# Rx_TSOP.net
KiCad netlist of a schematic drawn in Altium Designer
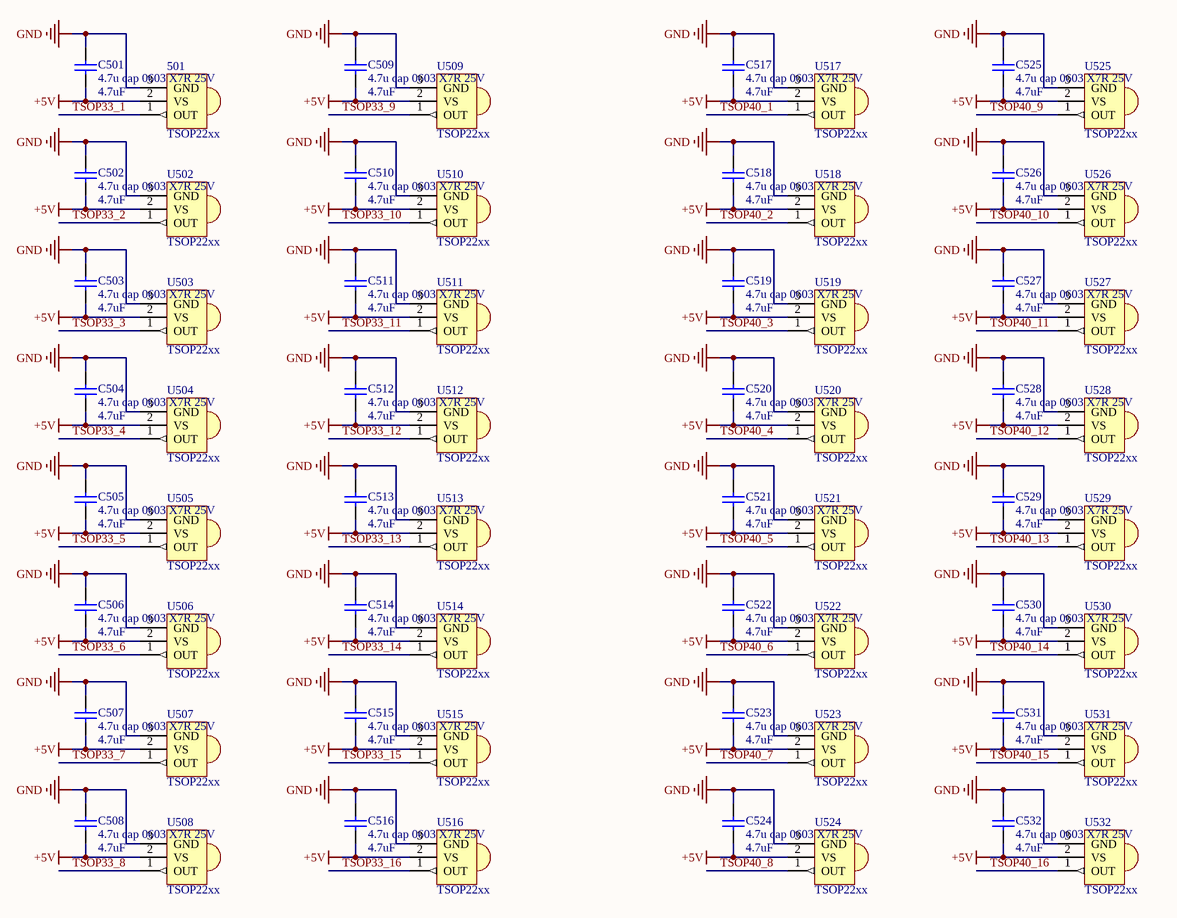
[diagram p0: Rx_TSOP.SchDoc]

(export (version "E")
  (design (tool "Eeschema 10.0.6"))
  (components
    (comp (ref "501")
      (value "TSOP22xx")
      (footprint "TSOP22xx")
      (description "IR Receiver Modules for Remote Control Systems")
      (libsource (lib "Oufff_Lib2") (part "TSOP22xx"))
    )
    (comp (ref "C501")
      (value "4.7u cap 0603 X7R 25V")
      (footprint "0603")
      (description "Capacitor")
      (fields (field (name "ALTIUM_VALUE") "4.7uF") (field (name "PUBLISHER") "Altium Limited"))
      (libsource (lib "Miscellaneous Devices") (part "Cap"))
    )
    (comp (ref "C502")
      (value "4.7u cap 0603 X7R 25V")
      (footprint "0603")
      (description "Capacitor")
      (fields (field (name "ALTIUM_VALUE") "4.7uF") (field (name "PUBLISHER") "Altium Limited"))
      (libsource (lib "Miscellaneous Devices") (part "Cap"))
    )
    (comp (ref "C503")
      (value "4.7u cap 0603 X7R 25V")
      (footprint "0603")
      (description "Capacitor")
      (fields (field (name "ALTIUM_VALUE") "4.7uF") (field (name "PUBLISHER") "Altium Limited"))
      (libsource (lib "Miscellaneous Devices") (part "Cap"))
    )
    (comp (ref "C504")
      (value "4.7u cap 0603 X7R 25V")
      (footprint "0603")
      (description "Capacitor")
      (fields (field (name "ALTIUM_VALUE") "4.7uF") (field (name "PUBLISHER") "Altium Limited"))
      (libsource (lib "Miscellaneous Devices") (part "Cap"))
    )
    (comp (ref "C505")
      (value "4.7u cap 0603 X7R 25V")
      (footprint "0603")
      (description "Capacitor")
      (fields (field (name "ALTIUM_VALUE") "4.7uF") (field (name "PUBLISHER") "Altium Limited"))
      (libsource (lib "Miscellaneous Devices") (part "Cap"))
    )
    (comp (ref "C506")
      (value "4.7u cap 0603 X7R 25V")
      (footprint "0603")
      (description "Capacitor")
      (fields (field (name "ALTIUM_VALUE") "4.7uF") (field (name "PUBLISHER") "Altium Limited"))
      (libsource (lib "Miscellaneous Devices") (part "Cap"))
    )
    (comp (ref "C507")
      (value "4.7u cap 0603 X7R 25V")
      (footprint "0603")
      (description "Capacitor")
      (fields (field (name "ALTIUM_VALUE") "4.7uF") (field (name "PUBLISHER") "Altium Limited"))
      (libsource (lib "Miscellaneous Devices") (part "Cap"))
    )
    (comp (ref "C508")
      (value "4.7u cap 0603 X7R 25V")
      (footprint "0603")
      (description "Capacitor")
      (fields (field (name "ALTIUM_VALUE") "4.7uF") (field (name "PUBLISHER") "Altium Limited"))
      (libsource (lib "Miscellaneous Devices") (part "Cap"))
    )
    (comp (ref "C509")
      (value "4.7u cap 0603 X7R 25V")
      (footprint "0603")
      (description "Capacitor")
      (fields (field (name "ALTIUM_VALUE") "4.7uF") (field (name "PUBLISHER") "Altium Limited"))
      (libsource (lib "Miscellaneous Devices") (part "Cap"))
    )
    (comp (ref "C510")
      (value "4.7u cap 0603 X7R 25V")
      (footprint "0603")
      (description "Capacitor")
      (fields (field (name "ALTIUM_VALUE") "4.7uF") (field (name "PUBLISHER") "Altium Limited"))
      (libsource (lib "Miscellaneous Devices") (part "Cap"))
    )
    (comp (ref "C511")
      (value "4.7u cap 0603 X7R 25V")
      (footprint "0603")
      (description "Capacitor")
      (fields (field (name "ALTIUM_VALUE") "4.7uF") (field (name "PUBLISHER") "Altium Limited"))
      (libsource (lib "Miscellaneous Devices") (part "Cap"))
    )
    (comp (ref "C512")
      (value "4.7u cap 0603 X7R 25V")
      (footprint "0603")
      (description "Capacitor")
      (fields (field (name "ALTIUM_VALUE") "4.7uF") (field (name "PUBLISHER") "Altium Limited"))
      (libsource (lib "Miscellaneous Devices") (part "Cap"))
    )
    (comp (ref "C513")
      (value "4.7u cap 0603 X7R 25V")
      (footprint "0603")
      (description "Capacitor")
      (fields (field (name "ALTIUM_VALUE") "4.7uF") (field (name "PUBLISHER") "Altium Limited"))
      (libsource (lib "Miscellaneous Devices") (part "Cap"))
    )
    (comp (ref "C514")
      (value "4.7u cap 0603 X7R 25V")
      (footprint "0603")
      (description "Capacitor")
      (fields (field (name "ALTIUM_VALUE") "4.7uF") (field (name "PUBLISHER") "Altium Limited"))
      (libsource (lib "Miscellaneous Devices") (part "Cap"))
    )
    (comp (ref "C515")
      (value "4.7u cap 0603 X7R 25V")
      (footprint "0603")
      (description "Capacitor")
      (fields (field (name "ALTIUM_VALUE") "4.7uF") (field (name "PUBLISHER") "Altium Limited"))
      (libsource (lib "Miscellaneous Devices") (part "Cap"))
    )
    (comp (ref "C516")
      (value "4.7u cap 0603 X7R 25V")
      (footprint "0603")
      (description "Capacitor")
      (fields (field (name "ALTIUM_VALUE") "4.7uF") (field (name "PUBLISHER") "Altium Limited"))
      (libsource (lib "Miscellaneous Devices") (part "Cap"))
    )
    (comp (ref "C517")
      (value "4.7u cap 0603 X7R 25V")
      (footprint "0603")
      (description "Capacitor")
      (fields (field (name "ALTIUM_VALUE") "4.7uF") (field (name "PUBLISHER") "Altium Limited"))
      (libsource (lib "Miscellaneous Devices") (part "Cap"))
    )
    (comp (ref "C518")
      (value "4.7u cap 0603 X7R 25V")
      (footprint "0603")
      (description "Capacitor")
      (fields (field (name "ALTIUM_VALUE") "4.7uF") (field (name "PUBLISHER") "Altium Limited"))
      (libsource (lib "Miscellaneous Devices") (part "Cap"))
    )
    (comp (ref "C519")
      (value "4.7u cap 0603 X7R 25V")
      (footprint "0603")
      (description "Capacitor")
      (fields (field (name "ALTIUM_VALUE") "4.7uF") (field (name "PUBLISHER") "Altium Limited"))
      (libsource (lib "Miscellaneous Devices") (part "Cap"))
    )
    (comp (ref "C520")
      (value "4.7u cap 0603 X7R 25V")
      (footprint "0603")
      (description "Capacitor")
      (fields (field (name "ALTIUM_VALUE") "4.7uF") (field (name "PUBLISHER") "Altium Limited"))
      (libsource (lib "Miscellaneous Devices") (part "Cap"))
    )
    (comp (ref "C521")
      (value "4.7u cap 0603 X7R 25V")
      (footprint "0603")
      (description "Capacitor")
      (fields (field (name "ALTIUM_VALUE") "4.7uF") (field (name "PUBLISHER") "Altium Limited"))
      (libsource (lib "Miscellaneous Devices") (part "Cap"))
    )
    (comp (ref "C522")
      (value "4.7u cap 0603 X7R 25V")
      (footprint "0603")
      (description "Capacitor")
      (fields (field (name "ALTIUM_VALUE") "4.7uF") (field (name "PUBLISHER") "Altium Limited"))
      (libsource (lib "Miscellaneous Devices") (part "Cap"))
    )
    (comp (ref "C523")
      (value "4.7u cap 0603 X7R 25V")
      (footprint "0603")
      (description "Capacitor")
      (fields (field (name "ALTIUM_VALUE") "4.7uF") (field (name "PUBLISHER") "Altium Limited"))
      (libsource (lib "Miscellaneous Devices") (part "Cap"))
    )
    (comp (ref "C524")
      (value "4.7u cap 0603 X7R 25V")
      (footprint "0603")
      (description "Capacitor")
      (fields (field (name "ALTIUM_VALUE") "4.7uF") (field (name "PUBLISHER") "Altium Limited"))
      (libsource (lib "Miscellaneous Devices") (part "Cap"))
    )
    (comp (ref "C525")
      (value "4.7u cap 0603 X7R 25V")
      (footprint "0603")
      (description "Capacitor")
      (fields (field (name "ALTIUM_VALUE") "4.7uF") (field (name "PUBLISHER") "Altium Limited"))
      (libsource (lib "Miscellaneous Devices") (part "Cap"))
    )
    (comp (ref "C526")
      (value "4.7u cap 0603 X7R 25V")
      (footprint "0603")
      (description "Capacitor")
      (fields (field (name "ALTIUM_VALUE") "4.7uF") (field (name "PUBLISHER") "Altium Limited"))
      (libsource (lib "Miscellaneous Devices") (part "Cap"))
    )
    (comp (ref "C527")
      (value "4.7u cap 0603 X7R 25V")
      (footprint "0603")
      (description "Capacitor")
      (fields (field (name "ALTIUM_VALUE") "4.7uF") (field (name "PUBLISHER") "Altium Limited"))
      (libsource (lib "Miscellaneous Devices") (part "Cap"))
    )
    (comp (ref "C528")
      (value "4.7u cap 0603 X7R 25V")
      (footprint "0603")
      (description "Capacitor")
      (fields (field (name "ALTIUM_VALUE") "4.7uF") (field (name "PUBLISHER") "Altium Limited"))
      (libsource (lib "Miscellaneous Devices") (part "Cap"))
    )
    (comp (ref "C529")
      (value "4.7u cap 0603 X7R 25V")
      (footprint "0603")
      (description "Capacitor")
      (fields (field (name "ALTIUM_VALUE") "4.7uF") (field (name "PUBLISHER") "Altium Limited"))
      (libsource (lib "Miscellaneous Devices") (part "Cap"))
    )
    (comp (ref "C530")
      (value "4.7u cap 0603 X7R 25V")
      (footprint "0603")
      (description "Capacitor")
      (fields (field (name "ALTIUM_VALUE") "4.7uF") (field (name "PUBLISHER") "Altium Limited"))
      (libsource (lib "Miscellaneous Devices") (part "Cap"))
    )
    (comp (ref "C531")
      (value "4.7u cap 0603 X7R 25V")
      (footprint "0603")
      (description "Capacitor")
      (fields (field (name "ALTIUM_VALUE") "4.7uF") (field (name "PUBLISHER") "Altium Limited"))
      (libsource (lib "Miscellaneous Devices") (part "Cap"))
    )
    (comp (ref "C532")
      (value "4.7u cap 0603 X7R 25V")
      (footprint "0603")
      (description "Capacitor")
      (fields (field (name "ALTIUM_VALUE") "4.7uF") (field (name "PUBLISHER") "Altium Limited"))
      (libsource (lib "Miscellaneous Devices") (part "Cap"))
    )
    (comp (ref "U502")
      (value "TSOP22xx")
      (footprint "TSOP22xx")
      (description "IR Receiver Modules for Remote Control Systems")
      (libsource (lib "Oufff_Lib2") (part "TSOP22xx"))
    )
    (comp (ref "U503")
      (value "TSOP22xx")
      (footprint "TSOP22xx")
      (description "IR Receiver Modules for Remote Control Systems")
      (libsource (lib "Oufff_Lib2") (part "TSOP22xx"))
    )
    (comp (ref "U504")
      (value "TSOP22xx")
      (footprint "TSOP22xx")
      (description "IR Receiver Modules for Remote Control Systems")
      (libsource (lib "Oufff_Lib2") (part "TSOP22xx"))
    )
    (comp (ref "U505")
      (value "TSOP22xx")
      (footprint "TSOP22xx")
      (description "IR Receiver Modules for Remote Control Systems")
      (libsource (lib "Oufff_Lib2") (part "TSOP22xx"))
    )
    (comp (ref "U506")
      (value "TSOP22xx")
      (footprint "TSOP22xx")
      (description "IR Receiver Modules for Remote Control Systems")
      (libsource (lib "Oufff_Lib2") (part "TSOP22xx"))
    )
    (comp (ref "U507")
      (value "TSOP22xx")
      (footprint "TSOP22xx")
      (description "IR Receiver Modules for Remote Control Systems")
      (libsource (lib "Oufff_Lib2") (part "TSOP22xx"))
    )
    (comp (ref "U508")
      (value "TSOP22xx")
      (footprint "TSOP22xx")
      (description "IR Receiver Modules for Remote Control Systems")
      (libsource (lib "Oufff_Lib2") (part "TSOP22xx"))
    )
    (comp (ref "U509")
      (value "TSOP22xx")
      (footprint "TSOP22xx")
      (description "IR Receiver Modules for Remote Control Systems")
      (libsource (lib "Oufff_Lib2") (part "TSOP22xx"))
    )
    (comp (ref "U510")
      (value "TSOP22xx")
      (footprint "TSOP22xx")
      (description "IR Receiver Modules for Remote Control Systems")
      (libsource (lib "Oufff_Lib2") (part "TSOP22xx"))
    )
    (comp (ref "U511")
      (value "TSOP22xx")
      (footprint "TSOP22xx")
      (description "IR Receiver Modules for Remote Control Systems")
      (libsource (lib "Oufff_Lib2") (part "TSOP22xx"))
    )
    (comp (ref "U512")
      (value "TSOP22xx")
      (footprint "TSOP22xx")
      (description "IR Receiver Modules for Remote Control Systems")
      (libsource (lib "Oufff_Lib2") (part "TSOP22xx"))
    )
    (comp (ref "U513")
      (value "TSOP22xx")
      (footprint "TSOP22xx")
      (description "IR Receiver Modules for Remote Control Systems")
      (libsource (lib "Oufff_Lib2") (part "TSOP22xx"))
    )
    (comp (ref "U514")
      (value "TSOP22xx")
      (footprint "TSOP22xx")
      (description "IR Receiver Modules for Remote Control Systems")
      (libsource (lib "Oufff_Lib2") (part "TSOP22xx"))
    )
    (comp (ref "U515")
      (value "TSOP22xx")
      (footprint "TSOP22xx")
      (description "IR Receiver Modules for Remote Control Systems")
      (libsource (lib "Oufff_Lib2") (part "TSOP22xx"))
    )
    (comp (ref "U516")
      (value "TSOP22xx")
      (footprint "TSOP22xx")
      (description "IR Receiver Modules for Remote Control Systems")
      (libsource (lib "Oufff_Lib2") (part "TSOP22xx"))
    )
    (comp (ref "U517")
      (value "TSOP22xx")
      (footprint "TSOP22xx")
      (description "IR Receiver Modules for Remote Control Systems")
      (libsource (lib "Oufff_Lib2") (part "TSOP22xx"))
    )
    (comp (ref "U518")
      (value "TSOP22xx")
      (footprint "TSOP22xx")
      (description "IR Receiver Modules for Remote Control Systems")
      (libsource (lib "Oufff_Lib2") (part "TSOP22xx"))
    )
    (comp (ref "U519")
      (value "TSOP22xx")
      (footprint "TSOP22xx")
      (description "IR Receiver Modules for Remote Control Systems")
      (libsource (lib "Oufff_Lib2") (part "TSOP22xx"))
    )
    (comp (ref "U520")
      (value "TSOP22xx")
      (footprint "TSOP22xx")
      (description "IR Receiver Modules for Remote Control Systems")
      (libsource (lib "Oufff_Lib2") (part "TSOP22xx"))
    )
    (comp (ref "U521")
      (value "TSOP22xx")
      (footprint "TSOP22xx")
      (description "IR Receiver Modules for Remote Control Systems")
      (libsource (lib "Oufff_Lib2") (part "TSOP22xx"))
    )
    (comp (ref "U522")
      (value "TSOP22xx")
      (footprint "TSOP22xx")
      (description "IR Receiver Modules for Remote Control Systems")
      (libsource (lib "Oufff_Lib2") (part "TSOP22xx"))
    )
    (comp (ref "U523")
      (value "TSOP22xx")
      (footprint "TSOP22xx")
      (description "IR Receiver Modules for Remote Control Systems")
      (libsource (lib "Oufff_Lib2") (part "TSOP22xx"))
    )
    (comp (ref "U524")
      (value "TSOP22xx")
      (footprint "TSOP22xx")
      (description "IR Receiver Modules for Remote Control Systems")
      (libsource (lib "Oufff_Lib2") (part "TSOP22xx"))
    )
    (comp (ref "U525")
      (value "TSOP22xx")
      (footprint "TSOP22xx")
      (description "IR Receiver Modules for Remote Control Systems")
      (libsource (lib "Oufff_Lib2") (part "TSOP22xx"))
    )
    (comp (ref "U526")
      (value "TSOP22xx")
      (footprint "TSOP22xx")
      (description "IR Receiver Modules for Remote Control Systems")
      (libsource (lib "Oufff_Lib2") (part "TSOP22xx"))
    )
    (comp (ref "U527")
      (value "TSOP22xx")
      (footprint "TSOP22xx")
      (description "IR Receiver Modules for Remote Control Systems")
      (libsource (lib "Oufff_Lib2") (part "TSOP22xx"))
    )
    (comp (ref "U528")
      (value "TSOP22xx")
      (footprint "TSOP22xx")
      (description "IR Receiver Modules for Remote Control Systems")
      (libsource (lib "Oufff_Lib2") (part "TSOP22xx"))
    )
    (comp (ref "U529")
      (value "TSOP22xx")
      (footprint "TSOP22xx")
      (description "IR Receiver Modules for Remote Control Systems")
      (libsource (lib "Oufff_Lib2") (part "TSOP22xx"))
    )
    (comp (ref "U530")
      (value "TSOP22xx")
      (footprint "TSOP22xx")
      (description "IR Receiver Modules for Remote Control Systems")
      (libsource (lib "Oufff_Lib2") (part "TSOP22xx"))
    )
    (comp (ref "U531")
      (value "TSOP22xx")
      (footprint "TSOP22xx")
      (description "IR Receiver Modules for Remote Control Systems")
      (libsource (lib "Oufff_Lib2") (part "TSOP22xx"))
    )
    (comp (ref "U532")
      (value "TSOP22xx")
      (footprint "TSOP22xx")
      (description "IR Receiver Modules for Remote Control Systems")
      (libsource (lib "Oufff_Lib2") (part "TSOP22xx"))
    )
  )
  (nets
    (net (code "1") (name "+5V") (class "Default")
      (node (ref "501") (pin "2") (pinfunction "VS_2") (pintype "power_in"))
      (node (ref "C501") (pin "1") (pinfunction "1_1") (pintype "passive"))
      (node (ref "C502") (pin "1") (pinfunction "1_1") (pintype "passive"))
      (node (ref "C503") (pin "1") (pinfunction "1_1") (pintype "passive"))
      (node (ref "C504") (pin "1") (pinfunction "1_1") (pintype "passive"))
      (node (ref "C505") (pin "1") (pinfunction "1_1") (pintype "passive"))
      (node (ref "C506") (pin "1") (pinfunction "1_1") (pintype "passive"))
      (node (ref "C507") (pin "1") (pinfunction "1_1") (pintype "passive"))
      (node (ref "C508") (pin "1") (pinfunction "1_1") (pintype "passive"))
      (node (ref "C509") (pin "1") (pinfunction "1_1") (pintype "passive"))
      (node (ref "C510") (pin "1") (pinfunction "1_1") (pintype "passive"))
      (node (ref "C511") (pin "1") (pinfunction "1_1") (pintype "passive"))
      (node (ref "C512") (pin "1") (pinfunction "1_1") (pintype "passive"))
      (node (ref "C513") (pin "1") (pinfunction "1_1") (pintype "passive"))
      (node (ref "C514") (pin "1") (pinfunction "1_1") (pintype "passive"))
      (node (ref "C515") (pin "1") (pinfunction "1_1") (pintype "passive"))
      (node (ref "C516") (pin "1") (pinfunction "1_1") (pintype "passive"))
      (node (ref "C517") (pin "1") (pinfunction "1_1") (pintype "passive"))
      (node (ref "C518") (pin "1") (pinfunction "1_1") (pintype "passive"))
      (node (ref "C519") (pin "1") (pinfunction "1_1") (pintype "passive"))
      (node (ref "C520") (pin "1") (pinfunction "1_1") (pintype "passive"))
      (node (ref "C521") (pin "1") (pinfunction "1_1") (pintype "passive"))
      (node (ref "C522") (pin "1") (pinfunction "1_1") (pintype "passive"))
      (node (ref "C523") (pin "1") (pinfunction "1_1") (pintype "passive"))
      (node (ref "C524") (pin "1") (pinfunction "1_1") (pintype "passive"))
      (node (ref "C525") (pin "1") (pinfunction "1_1") (pintype "passive"))
      (node (ref "C526") (pin "1") (pinfunction "1_1") (pintype "passive"))
      (node (ref "C527") (pin "1") (pinfunction "1_1") (pintype "passive"))
      (node (ref "C528") (pin "1") (pinfunction "1_1") (pintype "passive"))
      (node (ref "C529") (pin "1") (pinfunction "1_1") (pintype "passive"))
      (node (ref "C530") (pin "1") (pinfunction "1_1") (pintype "passive"))
      (node (ref "C531") (pin "1") (pinfunction "1_1") (pintype "passive"))
      (node (ref "C532") (pin "1") (pinfunction "1_1") (pintype "passive"))
      (node (ref "U502") (pin "2") (pinfunction "VS_2") (pintype "power_in"))
      (node (ref "U503") (pin "2") (pinfunction "VS_2") (pintype "power_in"))
      (node (ref "U504") (pin "2") (pinfunction "VS_2") (pintype "power_in"))
      (node (ref "U505") (pin "2") (pinfunction "VS_2") (pintype "power_in"))
      (node (ref "U506") (pin "2") (pinfunction "VS_2") (pintype "power_in"))
      (node (ref "U507") (pin "2") (pinfunction "VS_2") (pintype "power_in"))
      (node (ref "U508") (pin "2") (pinfunction "VS_2") (pintype "power_in"))
      (node (ref "U509") (pin "2") (pinfunction "VS_2") (pintype "power_in"))
      (node (ref "U510") (pin "2") (pinfunction "VS_2") (pintype "power_in"))
      (node (ref "U511") (pin "2") (pinfunction "VS_2") (pintype "power_in"))
      (node (ref "U512") (pin "2") (pinfunction "VS_2") (pintype "power_in"))
      (node (ref "U513") (pin "2") (pinfunction "VS_2") (pintype "power_in"))
      (node (ref "U514") (pin "2") (pinfunction "VS_2") (pintype "power_in"))
      (node (ref "U515") (pin "2") (pinfunction "VS_2") (pintype "power_in"))
      (node (ref "U516") (pin "2") (pinfunction "VS_2") (pintype "power_in"))
      (node (ref "U517") (pin "2") (pinfunction "VS_2") (pintype "power_in"))
      (node (ref "U518") (pin "2") (pinfunction "VS_2") (pintype "power_in"))
      (node (ref "U519") (pin "2") (pinfunction "VS_2") (pintype "power_in"))
      (node (ref "U520") (pin "2") (pinfunction "VS_2") (pintype "power_in"))
      (node (ref "U521") (pin "2") (pinfunction "VS_2") (pintype "power_in"))
      (node (ref "U522") (pin "2") (pinfunction "VS_2") (pintype "power_in"))
      (node (ref "U523") (pin "2") (pinfunction "VS_2") (pintype "power_in"))
      (node (ref "U524") (pin "2") (pinfunction "VS_2") (pintype "power_in"))
      (node (ref "U525") (pin "2") (pinfunction "VS_2") (pintype "power_in"))
      (node (ref "U526") (pin "2") (pinfunction "VS_2") (pintype "power_in"))
      (node (ref "U527") (pin "2") (pinfunction "VS_2") (pintype "power_in"))
      (node (ref "U528") (pin "2") (pinfunction "VS_2") (pintype "power_in"))
      (node (ref "U529") (pin "2") (pinfunction "VS_2") (pintype "power_in"))
      (node (ref "U530") (pin "2") (pinfunction "VS_2") (pintype "power_in"))
      (node (ref "U531") (pin "2") (pinfunction "VS_2") (pintype "power_in"))
      (node (ref "U532") (pin "2") (pinfunction "VS_2") (pintype "power_in"))
    )
    (net (code "2") (name "/TSOP33_1") (class "Default")
      (node (ref "501") (pin "1") (pinfunction "OUT_1") (pintype "output"))
    )
    (net (code "3") (name "/TSOP33_2") (class "Default")
      (node (ref "U502") (pin "1") (pinfunction "OUT_1") (pintype "output"))
    )
    (net (code "4") (name "/TSOP33_3") (class "Default")
      (node (ref "U503") (pin "1") (pinfunction "OUT_1") (pintype "output"))
    )
    (net (code "5") (name "/TSOP33_4") (class "Default")
      (node (ref "U504") (pin "1") (pinfunction "OUT_1") (pintype "output"))
    )
    (net (code "6") (name "/TSOP33_5") (class "Default")
      (node (ref "U505") (pin "1") (pinfunction "OUT_1") (pintype "output"))
    )
    (net (code "7") (name "/TSOP33_6") (class "Default")
      (node (ref "U506") (pin "1") (pinfunction "OUT_1") (pintype "output"))
    )
    (net (code "8") (name "/TSOP33_7") (class "Default")
      (node (ref "U507") (pin "1") (pinfunction "OUT_1") (pintype "output"))
    )
    (net (code "9") (name "/TSOP33_8") (class "Default")
      (node (ref "U508") (pin "1") (pinfunction "OUT_1") (pintype "output"))
    )
    (net (code "10") (name "/TSOP33_9") (class "Default")
      (node (ref "U509") (pin "1") (pinfunction "OUT_1") (pintype "output"))
    )
    (net (code "11") (name "/TSOP33_10") (class "Default")
      (node (ref "U510") (pin "1") (pinfunction "OUT_1") (pintype "output"))
    )
    (net (code "12") (name "/TSOP33_11") (class "Default")
      (node (ref "U511") (pin "1") (pinfunction "OUT_1") (pintype "output"))
    )
    (net (code "13") (name "/TSOP33_12") (class "Default")
      (node (ref "U512") (pin "1") (pinfunction "OUT_1") (pintype "output"))
    )
    (net (code "14") (name "/TSOP33_13") (class "Default")
      (node (ref "U513") (pin "1") (pinfunction "OUT_1") (pintype "output"))
    )
    (net (code "15") (name "/TSOP33_14") (class "Default")
      (node (ref "U514") (pin "1") (pinfunction "OUT_1") (pintype "output"))
    )
    (net (code "16") (name "/TSOP33_15") (class "Default")
      (node (ref "U515") (pin "1") (pinfunction "OUT_1") (pintype "output"))
    )
    (net (code "17") (name "/TSOP33_16") (class "Default")
      (node (ref "U516") (pin "1") (pinfunction "OUT_1") (pintype "output"))
    )
    (net (code "18") (name "/TSOP40_1") (class "Default")
      (node (ref "U517") (pin "1") (pinfunction "OUT_1") (pintype "output"))
    )
    (net (code "19") (name "/TSOP40_2") (class "Default")
      (node (ref "U518") (pin "1") (pinfunction "OUT_1") (pintype "output"))
    )
    (net (code "20") (name "/TSOP40_3") (class "Default")
      (node (ref "U519") (pin "1") (pinfunction "OUT_1") (pintype "output"))
    )
    (net (code "21") (name "/TSOP40_4") (class "Default")
      (node (ref "U520") (pin "1") (pinfunction "OUT_1") (pintype "output"))
    )
    (net (code "22") (name "/TSOP40_5") (class "Default")
      (node (ref "U521") (pin "1") (pinfunction "OUT_1") (pintype "output"))
    )
    (net (code "23") (name "/TSOP40_6") (class "Default")
      (node (ref "U522") (pin "1") (pinfunction "OUT_1") (pintype "output"))
    )
    (net (code "24") (name "/TSOP40_7") (class "Default")
      (node (ref "U523") (pin "1") (pinfunction "OUT_1") (pintype "output"))
    )
    (net (code "25") (name "/TSOP40_8") (class "Default")
      (node (ref "U524") (pin "1") (pinfunction "OUT_1") (pintype "output"))
    )
    (net (code "26") (name "/TSOP40_9") (class "Default")
      (node (ref "U525") (pin "1") (pinfunction "OUT_1") (pintype "output"))
    )
    (net (code "27") (name "/TSOP40_10") (class "Default")
      (node (ref "U526") (pin "1") (pinfunction "OUT_1") (pintype "output"))
    )
    (net (code "28") (name "/TSOP40_11") (class "Default")
      (node (ref "U527") (pin "1") (pinfunction "OUT_1") (pintype "output"))
    )
    (net (code "29") (name "/TSOP40_12") (class "Default")
      (node (ref "U528") (pin "1") (pinfunction "OUT_1") (pintype "output"))
    )
    (net (code "30") (name "/TSOP40_13") (class "Default")
      (node (ref "U529") (pin "1") (pinfunction "OUT_1") (pintype "output"))
    )
    (net (code "31") (name "/TSOP40_14") (class "Default")
      (node (ref "U530") (pin "1") (pinfunction "OUT_1") (pintype "output"))
    )
    (net (code "32") (name "/TSOP40_15") (class "Default")
      (node (ref "U531") (pin "1") (pinfunction "OUT_1") (pintype "output"))
    )
    (net (code "33") (name "/TSOP40_16") (class "Default")
      (node (ref "U532") (pin "1") (pinfunction "OUT_1") (pintype "output"))
    )
    (net (code "34") (name "GND") (class "Default")
      (node (ref "501") (pin "3") (pinfunction "GND_3") (pintype "power_in"))
      (node (ref "C501") (pin "2") (pinfunction "2_2") (pintype "passive"))
      (node (ref "C502") (pin "2") (pinfunction "2_2") (pintype "passive"))
      (node (ref "C503") (pin "2") (pinfunction "2_2") (pintype "passive"))
      (node (ref "C504") (pin "2") (pinfunction "2_2") (pintype "passive"))
      (node (ref "C505") (pin "2") (pinfunction "2_2") (pintype "passive"))
      (node (ref "C506") (pin "2") (pinfunction "2_2") (pintype "passive"))
      (node (ref "C507") (pin "2") (pinfunction "2_2") (pintype "passive"))
      (node (ref "C508") (pin "2") (pinfunction "2_2") (pintype "passive"))
      (node (ref "C509") (pin "2") (pinfunction "2_2") (pintype "passive"))
      (node (ref "C510") (pin "2") (pinfunction "2_2") (pintype "passive"))
      (node (ref "C511") (pin "2") (pinfunction "2_2") (pintype "passive"))
      (node (ref "C512") (pin "2") (pinfunction "2_2") (pintype "passive"))
      (node (ref "C513") (pin "2") (pinfunction "2_2") (pintype "passive"))
      (node (ref "C514") (pin "2") (pinfunction "2_2") (pintype "passive"))
      (node (ref "C515") (pin "2") (pinfunction "2_2") (pintype "passive"))
      (node (ref "C516") (pin "2") (pinfunction "2_2") (pintype "passive"))
      (node (ref "C517") (pin "2") (pinfunction "2_2") (pintype "passive"))
      (node (ref "C518") (pin "2") (pinfunction "2_2") (pintype "passive"))
      (node (ref "C519") (pin "2") (pinfunction "2_2") (pintype "passive"))
      (node (ref "C520") (pin "2") (pinfunction "2_2") (pintype "passive"))
      (node (ref "C521") (pin "2") (pinfunction "2_2") (pintype "passive"))
      (node (ref "C522") (pin "2") (pinfunction "2_2") (pintype "passive"))
      (node (ref "C523") (pin "2") (pinfunction "2_2") (pintype "passive"))
      (node (ref "C524") (pin "2") (pinfunction "2_2") (pintype "passive"))
      (node (ref "C525") (pin "2") (pinfunction "2_2") (pintype "passive"))
      (node (ref "C526") (pin "2") (pinfunction "2_2") (pintype "passive"))
      (node (ref "C527") (pin "2") (pinfunction "2_2") (pintype "passive"))
      (node (ref "C528") (pin "2") (pinfunction "2_2") (pintype "passive"))
      (node (ref "C529") (pin "2") (pinfunction "2_2") (pintype "passive"))
      (node (ref "C530") (pin "2") (pinfunction "2_2") (pintype "passive"))
      (node (ref "C531") (pin "2") (pinfunction "2_2") (pintype "passive"))
      (node (ref "C532") (pin "2") (pinfunction "2_2") (pintype "passive"))
      (node (ref "U502") (pin "3") (pinfunction "GND_3") (pintype "power_in"))
      (node (ref "U503") (pin "3") (pinfunction "GND_3") (pintype "power_in"))
      (node (ref "U504") (pin "3") (pinfunction "GND_3") (pintype "power_in"))
      (node (ref "U505") (pin "3") (pinfunction "GND_3") (pintype "power_in"))
      (node (ref "U506") (pin "3") (pinfunction "GND_3") (pintype "power_in"))
      (node (ref "U507") (pin "3") (pinfunction "GND_3") (pintype "power_in"))
      (node (ref "U508") (pin "3") (pinfunction "GND_3") (pintype "power_in"))
      (node (ref "U509") (pin "3") (pinfunction "GND_3") (pintype "power_in"))
      (node (ref "U510") (pin "3") (pinfunction "GND_3") (pintype "power_in"))
      (node (ref "U511") (pin "3") (pinfunction "GND_3") (pintype "power_in"))
      (node (ref "U512") (pin "3") (pinfunction "GND_3") (pintype "power_in"))
      (node (ref "U513") (pin "3") (pinfunction "GND_3") (pintype "power_in"))
      (node (ref "U514") (pin "3") (pinfunction "GND_3") (pintype "power_in"))
      (node (ref "U515") (pin "3") (pinfunction "GND_3") (pintype "power_in"))
      (node (ref "U516") (pin "3") (pinfunction "GND_3") (pintype "power_in"))
      (node (ref "U517") (pin "3") (pinfunction "GND_3") (pintype "power_in"))
      (node (ref "U518") (pin "3") (pinfunction "GND_3") (pintype "power_in"))
      (node (ref "U519") (pin "3") (pinfunction "GND_3") (pintype "power_in"))
      (node (ref "U520") (pin "3") (pinfunction "GND_3") (pintype "power_in"))
      (node (ref "U521") (pin "3") (pinfunction "GND_3") (pintype "power_in"))
      (node (ref "U522") (pin "3") (pinfunction "GND_3") (pintype "power_in"))
      (node (ref "U523") (pin "3") (pinfunction "GND_3") (pintype "power_in"))
      (node (ref "U524") (pin "3") (pinfunction "GND_3") (pintype "power_in"))
      (node (ref "U525") (pin "3") (pinfunction "GND_3") (pintype "power_in"))
      (node (ref "U526") (pin "3") (pinfunction "GND_3") (pintype "power_in"))
      (node (ref "U527") (pin "3") (pinfunction "GND_3") (pintype "power_in"))
      (node (ref "U528") (pin "3") (pinfunction "GND_3") (pintype "power_in"))
      (node (ref "U529") (pin "3") (pinfunction "GND_3") (pintype "power_in"))
      (node (ref "U530") (pin "3") (pinfunction "GND_3") (pintype "power_in"))
      (node (ref "U531") (pin "3") (pinfunction "GND_3") (pintype "power_in"))
      (node (ref "U532") (pin "3") (pinfunction "GND_3") (pintype "power_in"))
    )
  )
)
